# Power.net
KiCad netlist of a schematic drawn in Altium Designer
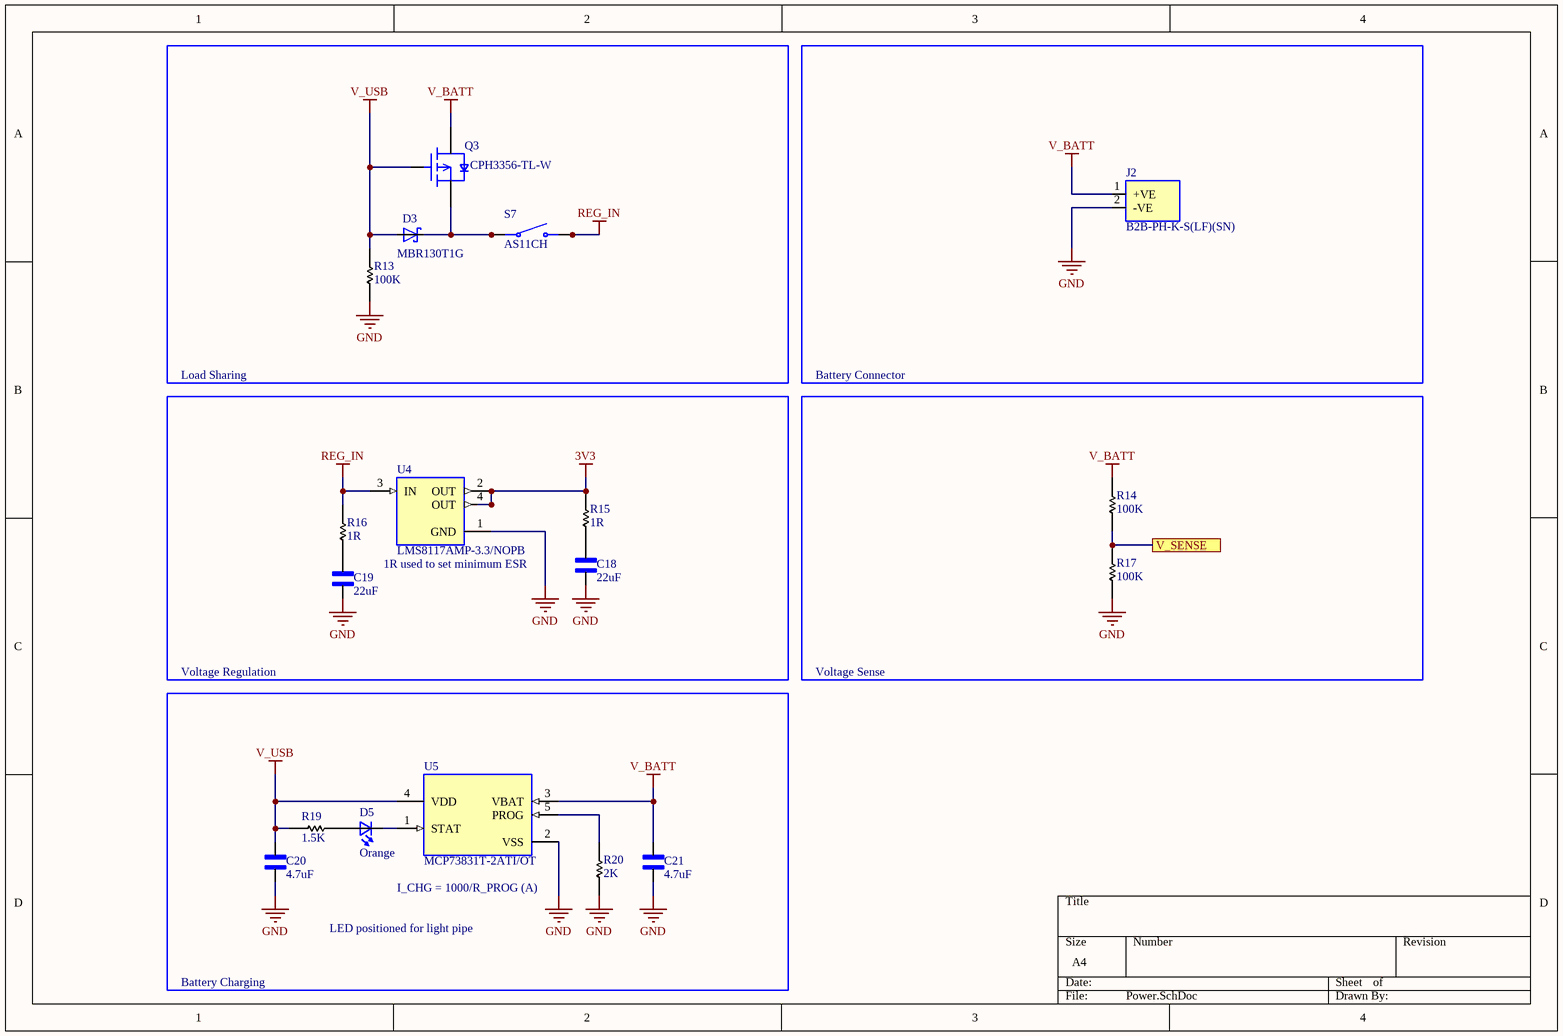
[diagram p0: Power.SchDoc]

(export (version "E")
  (design (tool "Eeschema 10.0.6"))
  (components
    (comp (ref "C18")
      (value "22uF")
      (footprint "CHIP_0603")
      (description "Generic 0603 Ceramic Capacitor")
      (fields (field (name "MP") "AC0402FR-071ML") (field (name "MF") "Yageo"))
      (libsource (lib "Guitar_Multi_Effect_lib") (part "0603 Ceramic Capacitor"))
    )
    (comp (ref "C19")
      (value "22uF")
      (footprint "CHIP_0603")
      (description "Generic 0603 Ceramic Capacitor")
      (fields (field (name "MP") "AC0402FR-071ML") (field (name "MF") "Yageo"))
      (libsource (lib "Guitar_Multi_Effect_lib") (part "0603 Ceramic Capacitor"))
    )
    (comp (ref "C20")
      (value "4.7uF")
      (footprint "CHIP_0603")
      (description "Generic 0603 Ceramic Capacitor")
      (fields (field (name "MP") "AC0402FR-071ML") (field (name "MF") "Yageo"))
      (libsource (lib "Guitar_Multi_Effect_lib") (part "0603 Ceramic Capacitor"))
    )
    (comp (ref "C21")
      (value "4.7uF")
      (footprint "CHIP_0603")
      (description "Generic 0603 Ceramic Capacitor")
      (fields (field (name "MP") "AC0402FR-071ML") (field (name "MF") "Yageo"))
      (libsource (lib "Guitar_Multi_Effect_lib") (part "0603 Ceramic Capacitor"))
    )
    (comp (ref "D3")
      (value "MBR130T1G")
      (footprint "Multi_Effect_Interface_lib:SOD-123-2")
      (description "Diode Schottky 30 V 1A Surface Mount SOD-123")
      (fields (field (name "MP") "MBR0530") (field (name "MF") "ON Semiconductor"))
      (libsource (lib "Guitar_Multi_Effect_Interface_lib") (part "MBR130T1G"))
    )
    (comp (ref "D5")
      (value "Orange")
      (footprint "0603 LED Generic")
      (description "0603 Generic LED")
      (libsource (lib "Guitar_Multi_Effect_Interface_lib") (part "0603 Generic LED"))
    )
    (comp (ref "J2")
      (value "B2B-PH-K-S(LF)(SN)")
      (footprint "Multi_Effect_Interface_lib:JST_B2B-PH-K-S(LF)(SN)")
      (description "Connector Header Through Hole 2 position 0.079\" (2.00mm)")
      (fields (field (name "MP") "S2B-PH-SM4-TB_LF__SN_") (field (name "MF") "JST Sales"))
      (libsource (lib "Guitar_Multi_Effect_Interface_lib") (part "B2B-PH-K-S(LF)(SN)"))
    )
    (comp (ref "Q3")
      (value "CPH3356-TL-W")
      (footprint "SOT23-3")
      (description "P-Channel 20 V 2.5A (Ta) 1W (Ta) Surface Mount 3-CPH")
      (libsource (lib "Guitar_Multi_Effect_Interface_lib") (part "CPH3356-TL-W"))
    )
    (comp (ref "R13")
      (value "100K")
      (footprint "CHIP_R_0603")
      (description "Generic 0603 Resistor")
      (libsource (lib "Guitar_Multi_Effect_lib") (part "0603 Generic Resistor"))
    )
    (comp (ref "R14")
      (value "100K")
      (footprint "CHIP_R_0603")
      (description "Generic 0603 Resistor")
      (libsource (lib "Guitar_Multi_Effect_lib") (part "0603 Generic Resistor"))
    )
    (comp (ref "R15")
      (value "1R")
      (footprint "CHIP_R_0603")
      (description "Generic 0603 Resistor")
      (libsource (lib "Guitar_Multi_Effect_lib") (part "0603 Generic Resistor"))
    )
    (comp (ref "R16")
      (value "1R")
      (footprint "CHIP_R_0603")
      (description "Generic 0603 Resistor")
      (libsource (lib "Guitar_Multi_Effect_lib") (part "0603 Generic Resistor"))
    )
    (comp (ref "R17")
      (value "100K")
      (footprint "CHIP_R_0603")
      (description "Generic 0603 Resistor")
      (libsource (lib "Guitar_Multi_Effect_lib") (part "0603 Generic Resistor"))
    )
    (comp (ref "R19")
      (value "1.5K")
      (footprint "CHIP_R_0603")
      (description "Generic 0603 Resistor")
      (libsource (lib "Guitar_Multi_Effect_lib") (part "0603 Generic Resistor"))
    )
    (comp (ref "R20")
      (value "2K")
      (footprint "CHIP_R_0603")
      (description "Generic 0603 Resistor")
      (libsource (lib "Guitar_Multi_Effect_lib") (part "0603 Generic Resistor"))
    )
    (comp (ref "S7")
      (value "AS11CH")
      (footprint "AS11CH")
      (description "SWITCH SLIDE SPST 0.4VA 28V")
      (libsource (lib "Guitar_Multi_Effect_Interface_lib") (part "AS11CH"))
    )
    (comp (ref "U4")
      (value "LMS8117AMP-3.3/NOPB")
      (footprint "Multi_Effect_Interface_lib:SOT230P700X180-4N")
      (description "Fixed 3.3V LDO 1A 15V input SOT-223")
      (fields (field (name "MF") "Texas Instruments"))
      (libsource (lib "Guitar_Multi_Effect_Interface_lib") (part "LMS8117AMP-3.3/NOPB"))
    )
    (comp (ref "U5")
      (value "MCP73831T-2ATI/OT")
      (footprint "Multi_Effect_Interface_lib:SOT95P280X145-5N")
      (description "Charger IC Lithium Ion/Polymer SOT-23-5")
      (fields (field (name "MF") "Microchip"))
      (libsource (lib "Guitar_Multi_Effect_Interface_lib") (part "MCP73831T-2ATI/OT"))
    )
  )
  (nets
    (net (code "1") (name "/V_SENSE") (class "Default")
      (node (ref "R14") (pin "2") (pinfunction "2_2") (pintype "passive"))
      (node (ref "R17") (pin "1") (pinfunction "1_1") (pintype "passive"))
    )
    (net (code "2") (name "3V3") (class "Default")
      (node (ref "R15") (pin "1") (pinfunction "1_1") (pintype "passive"))
      (node (ref "U4") (pin "2") (pinfunction "OUT_2") (pintype "output"))
      (node (ref "U4") (pin "4") (pinfunction "OUT_4") (pintype "output"))
    )
    (net (code "3") (name "GND") (class "Default")
      (node (ref "C18") (pin "2") (pinfunction "2_2") (pintype "passive"))
      (node (ref "C19") (pin "2") (pinfunction "2_2") (pintype "passive"))
      (node (ref "C20") (pin "2") (pinfunction "2_2") (pintype "passive"))
      (node (ref "C21") (pin "2") (pinfunction "2_2") (pintype "passive"))
      (node (ref "J2") (pin "2") (pinfunction "-VE_2") (pintype "passive"))
      (node (ref "R13") (pin "2") (pinfunction "2_2") (pintype "passive"))
      (node (ref "R17") (pin "2") (pinfunction "2_2") (pintype "passive"))
      (node (ref "R20") (pin "2") (pinfunction "2_2") (pintype "passive"))
      (node (ref "U4") (pin "1") (pinfunction "GND_1") (pintype "power_in"))
      (node (ref "U5") (pin "2") (pinfunction "VSS_2") (pintype "power_in"))
    )
    (net (code "4") (name "Net-(C18-Pad1)") (class "Default")
      (node (ref "C18") (pin "1") (pinfunction "1_1") (pintype "passive"))
      (node (ref "R15") (pin "2") (pinfunction "2_2") (pintype "passive"))
    )
    (net (code "5") (name "Net-(C19-Pad1)") (class "Default")
      (node (ref "C19") (pin "1") (pinfunction "1_1") (pintype "passive"))
      (node (ref "R16") (pin "2") (pinfunction "2_2") (pintype "passive"))
    )
    (net (code "6") (name "Net-(D5-A2)") (class "Default")
      (node (ref "D5") (pin "2") (pinfunction "A2_2") (pintype "passive"))
      (node (ref "R19") (pin "2") (pinfunction "2_2") (pintype "passive"))
    )
    (net (code "7") (name "Net-(D5-K2)") (class "Default")
      (node (ref "D5") (pin "1") (pinfunction "K2_1") (pintype "passive"))
      (node (ref "U5") (pin "1") (pinfunction "STAT_1") (pintype "input"))
    )
    (net (code "8") (name "Net-(Q3-S)") (class "Default")
      (node (ref "D3") (pin "C") (pinfunction "C_C") (pintype "passive"))
      (node (ref "Q3") (pin "2") (pinfunction "S_2") (pintype "passive"))
      (node (ref "S7") (pin "1") (pinfunction "COM_1") (pintype "passive"))
      (node (ref "S7") (pin "3") (pinfunction "3_3") (pintype "passive"))
    )
    (net (code "9") (name "Net-(U5-PROG)") (class "Default")
      (node (ref "R20") (pin "1") (pinfunction "1_1") (pintype "passive"))
      (node (ref "U5") (pin "5") (pinfunction "PROG_5") (pintype "input"))
    )
    (net (code "10") (name "REG_IN") (class "Default")
      (node (ref "R16") (pin "1") (pinfunction "1_1") (pintype "passive"))
      (node (ref "S7") (pin "1") (pinfunction "1_1") (pintype "passive"))
      (node (ref "S7") (pin "3") (pinfunction "NO_3") (pintype "passive"))
      (node (ref "U4") (pin "3") (pinfunction "IN_3") (pintype "input"))
    )
    (net (code "11") (name "V_BATT") (class "Default")
      (node (ref "C21") (pin "1") (pinfunction "1_1") (pintype "passive"))
      (node (ref "J2") (pin "1") (pinfunction "+VE_1") (pintype "passive"))
      (node (ref "Q3") (pin "3") (pinfunction "D_3") (pintype "passive"))
      (node (ref "R14") (pin "1") (pinfunction "1_1") (pintype "passive"))
      (node (ref "U5") (pin "3") (pinfunction "VBAT_3") (pintype "input"))
    )
    (net (code "12") (name "V_USB") (class "Default")
      (node (ref "C20") (pin "1") (pinfunction "1_1") (pintype "passive"))
      (node (ref "D3") (pin "A") (pinfunction "A_A") (pintype "passive"))
      (node (ref "Q3") (pin "1") (pinfunction "G_1") (pintype "passive"))
      (node (ref "R13") (pin "1") (pinfunction "1_1") (pintype "passive"))
      (node (ref "R19") (pin "1") (pinfunction "1_1") (pintype "passive"))
      (node (ref "U5") (pin "4") (pinfunction "VDD_4") (pintype "power_in"))
    )
  )
)
